# Eagle_schem_Nepixel_MIC_1_ESP8266_12.net
KiCad netlist of a schematic drawn in EAGLE
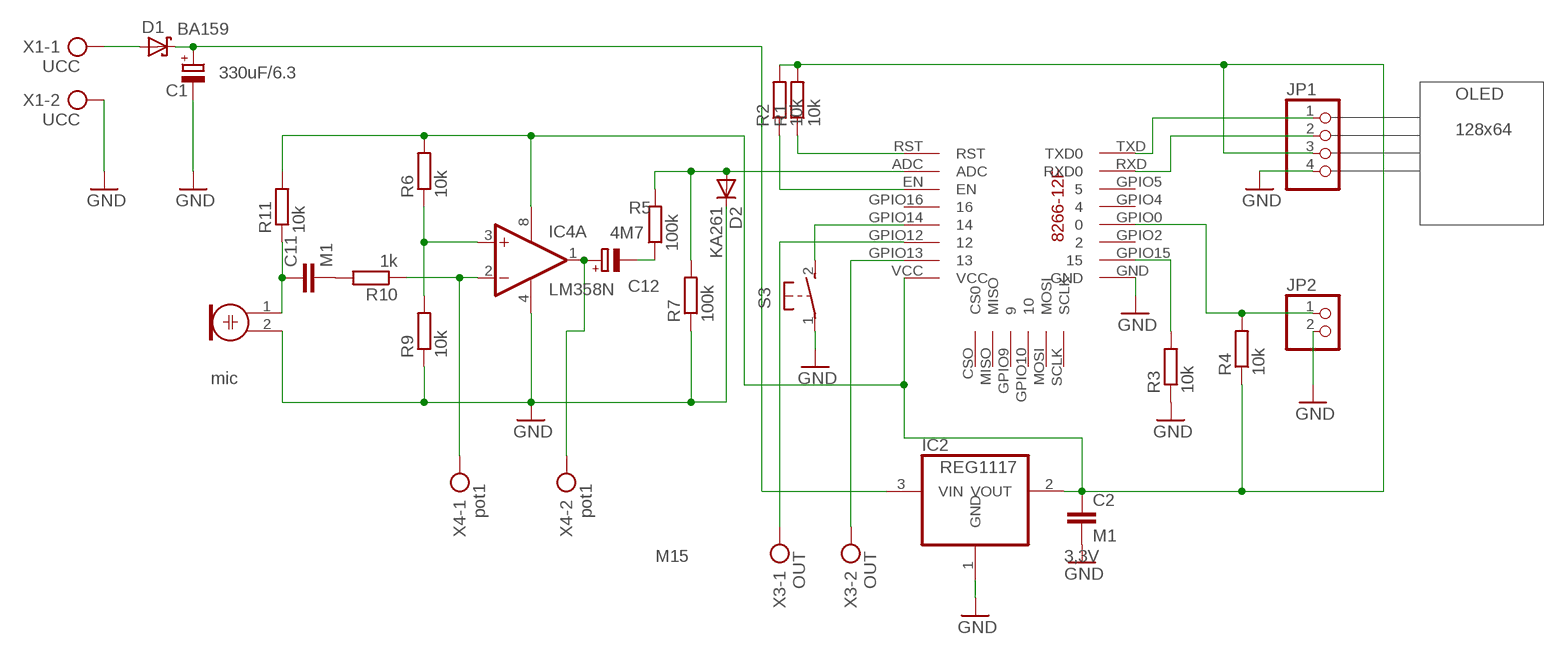
[diagram p0: schematic, sheet 1]

(export (version "E")
  (design (tool "Eeschema 10.0.6"))
  (components
    (comp (ref "C1")
      (value "330uF/6.3")
      (footprint "eagle-import:E2,5-7")
      (libsource (lib "eagle-import") (part "CPOL-EUE2.5-7"))
    )
    (comp (ref "C2")
      (value "M1")
      (footprint "eagle-import:C025-024X044")
      (libsource (lib "eagle-import") (part "C-EU025-024X044"))
    )
    (comp (ref "C11")
      (value "M1")
      (footprint "eagle-import:C025-024X044")
      (libsource (lib "eagle-import") (part "C-EU025-024X044"))
    )
    (comp (ref "C12")
      (value "4M7")
      (footprint "eagle-import:E2,5-5")
      (libsource (lib "eagle-import") (part "CPOL-EUE2.5-5"))
    )
    (comp (ref "D1")
      (value "BA159")
      (footprint "eagle-import:DO35-7")
      (libsource (lib "eagle-import") (part "SCHOTTKY-DIODEDO35-7"))
    )
    (comp (ref "D2")
      (value "KA261")
      (footprint "eagle-import:DO41-7.6")
      (libsource (lib "eagle-import") (part "DIODE-DO41-7.6"))
    )
    (comp (ref "IC2")
      (value "REG1117")
      (footprint "eagle-import:SOT223")
      (libsource (lib "eagle-import") (part "REG1117"))
    )
    (comp (ref "IC4")
      (value "LM358N")
      (footprint "eagle-import:DIL08")
      (libsource (lib "eagle-import") (part "LM358N"))
    )
    (comp (ref "JP1")
      (value "PINHD-1X4")
      (footprint "eagle-import:1X04")
      (libsource (lib "eagle-import") (part "PINHD-1X4"))
    )
    (comp (ref "JP2")
      (value "PINHD-1X2")
      (footprint "eagle-import:1X02")
      (libsource (lib "eagle-import") (part "PINHD-1X2"))
    )
    (comp (ref "M1")
      (value "mic")
      (footprint "eagle-import:WM-64PN")
      (libsource (lib "eagle-import") (part "ELECTRET_MICROPHON-WM.64PN"))
    )
    (comp (ref "R1")
      (value "10k")
      (footprint "eagle-import:0204_7")
      (libsource (lib "eagle-import") (part "R-EU_0204/7"))
    )
    (comp (ref "R2")
      (value "10k")
      (footprint "eagle-import:0204_7")
      (libsource (lib "eagle-import") (part "R-EU_0204/7"))
    )
    (comp (ref "R3")
      (value "10k")
      (footprint "eagle-import:0204_7")
      (libsource (lib "eagle-import") (part "R-EU_0204/7"))
    )
    (comp (ref "R4")
      (value "10k")
      (footprint "eagle-import:0204_7")
      (libsource (lib "eagle-import") (part "R-EU_0204/7"))
    )
    (comp (ref "R5")
      (value "100k")
      (footprint "eagle-import:0204_7")
      (libsource (lib "eagle-import") (part "R-EU_0204/7"))
    )
    (comp (ref "R6")
      (value "10k")
      (footprint "eagle-import:0204_7")
      (libsource (lib "eagle-import") (part "R-EU_0204/7"))
    )
    (comp (ref "R7")
      (value "100k")
      (footprint "eagle-import:0204_7")
      (libsource (lib "eagle-import") (part "R-EU_0204/7"))
    )
    (comp (ref "R9")
      (value "10k")
      (footprint "eagle-import:0204_7")
      (libsource (lib "eagle-import") (part "R-EU_0204/7"))
    )
    (comp (ref "R10")
      (value "1k")
      (footprint "eagle-import:0204_7")
      (libsource (lib "eagle-import") (part "R-EU_0204/7"))
    )
    (comp (ref "R11")
      (value "10k")
      (footprint "eagle-import:0204_7")
      (libsource (lib "eagle-import") (part "R-EU_0204/7"))
    )
    (comp (ref "S3")
      (value "31-XX")
      (footprint "eagle-import:B3F-31XX")
      (fields (field (name "MPN") "B3F-3100"))
      (libsource (lib "eagle-import") (part "31-XX"))
    )
    (comp (ref "U$1")
      (value "ESP826612F")
      (footprint "eagle-import:ESP826612F")
      (libsource (lib "eagle-import") (part "ESP826612F"))
    )
    (comp (ref "X1")
      (value "UCC")
      (footprint "eagle-import:AK550_2")
      (libsource (lib "eagle-import") (part "AK550/2"))
    )
    (comp (ref "X3")
      (value "OUT")
      (footprint "eagle-import:AK550_2")
      (fields (field (name "OC_FARNELL") "unknown") (field (name "OC_NEWARK") "unknown"))
      (libsource (lib "eagle-import") (part "AK550/2"))
    )
    (comp (ref "X4")
      (value "pot1")
      (footprint "eagle-import:AK550_2")
      (fields (field (name "OC_FARNELL") "unknown") (field (name "OC_NEWARK") "unknown"))
      (libsource (lib "eagle-import") (part "AK550/2"))
    )
  )
  (nets
    (net (code "1") (name "GND") (class "Default")
      (node (ref "C1") (pin "-") (pinfunction "-_-") (pintype "passive"))
      (node (ref "C2") (pin "2") (pinfunction "2_2") (pintype "passive"))
      (node (ref "D2") (pin "C") (pinfunction "C_C") (pintype "passive"))
      (node (ref "IC2") (pin "1") (pinfunction "GND_1") (pintype "power_in"))
      (node (ref "IC4") (pin "4") (pinfunction "V-_4") (pintype "power_in"))
      (node (ref "JP1") (pin "4") (pinfunction "4_4") (pintype "passive"))
      (node (ref "JP2") (pin "2") (pinfunction "2_2") (pintype "passive"))
      (node (ref "M1") (pin "2") (pinfunction "2_2") (pintype "passive"))
      (node (ref "R3") (pin "1") (pinfunction "1_1") (pintype "passive"))
      (node (ref "R7") (pin "1") (pinfunction "1_1") (pintype "passive"))
      (node (ref "R9") (pin "1") (pinfunction "1_1") (pintype "passive"))
      (node (ref "S3") (pin "1") (pinfunction "P_1") (pintype "passive"))
      (node (ref "U$1") (pin "GND") (pinfunction "GND_GND") (pintype "bidirectional"))
      (node (ref "X1") (pin "2") (pinfunction "KL_2") (pintype "passive"))
    )
    (net (code "2") (name "Net-(C11-Pad1)") (class "Default")
      (node (ref "C11") (pin "1") (pinfunction "1_1") (pintype "passive"))
      (node (ref "M1") (pin "1") (pinfunction "1_1") (pintype "passive"))
      (node (ref "R11") (pin "1") (pinfunction "1_1") (pintype "passive"))
    )
    (net (code "3") (name "Net-(C11-Pad2)") (class "Default")
      (node (ref "C11") (pin "2") (pinfunction "2_2") (pintype "passive"))
      (node (ref "R10") (pin "2") (pinfunction "2_2") (pintype "passive"))
    )
    (net (code "4") (name "Net-(C12-Pad-)") (class "Default")
      (node (ref "C12") (pin "-") (pinfunction "-_-") (pintype "passive"))
      (node (ref "R5") (pin "1") (pinfunction "1_1") (pintype "passive"))
    )
    (net (code "5") (name "Net-(D2-PadA)") (class "Default")
      (node (ref "D2") (pin "A") (pinfunction "A_A") (pintype "passive"))
      (node (ref "R5") (pin "2") (pinfunction "2_2") (pintype "passive"))
      (node (ref "R7") (pin "2") (pinfunction "2_2") (pintype "passive"))
      (node (ref "U$1") (pin "ADC") (pinfunction "ADC_ADC") (pintype "bidirectional"))
    )
    (net (code "6") (name "Net-(IC2-VIN)") (class "Default")
      (node (ref "C1") (pin "+") (pinfunction "+_+") (pintype "passive"))
      (node (ref "D1") (pin "C") (pinfunction "C_C") (pintype "passive"))
      (node (ref "IC2") (pin "3") (pinfunction "VIN_3") (pintype "input"))
    )
    (net (code "7") (name "Net-(IC2-VOUT)") (class "Default")
      (node (ref "C2") (pin "1") (pinfunction "1_1") (pintype "passive"))
      (node (ref "IC2") (pin "2") (pinfunction "VOUT_2") (pintype "output"))
      (node (ref "IC4") (pin "8") (pinfunction "V+_8") (pintype "power_in"))
      (node (ref "JP1") (pin "3") (pinfunction "3_3") (pintype "passive"))
      (node (ref "R1") (pin "2") (pinfunction "2_2") (pintype "passive"))
      (node (ref "R11") (pin "2") (pinfunction "2_2") (pintype "passive"))
      (node (ref "R2") (pin "2") (pinfunction "2_2") (pintype "passive"))
      (node (ref "R4") (pin "1") (pinfunction "1_1") (pintype "passive"))
      (node (ref "R6") (pin "2") (pinfunction "2_2") (pintype "passive"))
      (node (ref "U$1") (pin "VCC") (pinfunction "VCC_VCC") (pintype "bidirectional"))
    )
    (net (code "8") (name "Net-(IC4A-+IN)") (class "Default")
      (node (ref "IC4") (pin "3") (pinfunction "+IN_3") (pintype "input"))
      (node (ref "R6") (pin "1") (pinfunction "1_1") (pintype "passive"))
      (node (ref "R9") (pin "2") (pinfunction "2_2") (pintype "passive"))
    )
    (net (code "9") (name "Net-(IC4A--IN)") (class "Default")
      (node (ref "IC4") (pin "2") (pinfunction "-IN_2") (pintype "input"))
      (node (ref "R10") (pin "1") (pinfunction "1_1") (pintype "passive"))
      (node (ref "X4") (pin "1") (pinfunction "KL_1") (pintype "passive"))
    )
    (net (code "10") (name "Net-(IC4A-OUT)") (class "Default")
      (node (ref "C12") (pin "+") (pinfunction "+_+") (pintype "passive"))
      (node (ref "IC4") (pin "1") (pinfunction "OUT_1") (pintype "output"))
      (node (ref "X4") (pin "2") (pinfunction "KL_2") (pintype "passive"))
    )
    (net (code "11") (name "Net-(R1-Pad1)") (class "Default")
      (node (ref "R1") (pin "1") (pinfunction "1_1") (pintype "passive"))
      (node (ref "U$1") (pin "RST") (pinfunction "RST_RST") (pintype "bidirectional"))
    )
    (net (code "12") (name "Net-(R2-Pad1)") (class "Default")
      (node (ref "R2") (pin "1") (pinfunction "1_1") (pintype "passive"))
      (node (ref "U$1") (pin "EN") (pinfunction "EN_EN") (pintype "bidirectional"))
    )
    (net (code "13") (name "Net-(S3-S)") (class "Default")
      (node (ref "S3") (pin "2") (pinfunction "S_2") (pintype "passive"))
      (node (ref "U$1") (pin "GPIO14") (pinfunction "14_GPIO14") (pintype "bidirectional"))
    )
    (net (code "14") (name "Net-(U$1-0)") (class "Default")
      (node (ref "JP2") (pin "1") (pinfunction "1_1") (pintype "passive"))
      (node (ref "R4") (pin "2") (pinfunction "2_2") (pintype "passive"))
      (node (ref "U$1") (pin "GPIO0") (pinfunction "0_GPIO0") (pintype "bidirectional"))
    )
    (net (code "15") (name "Net-(U$1-12)") (class "Default")
      (node (ref "U$1") (pin "GPIO12") (pinfunction "12_GPIO12") (pintype "bidirectional"))
      (node (ref "X3") (pin "1") (pinfunction "KL_1") (pintype "passive"))
    )
    (net (code "16") (name "Net-(U$1-13)") (class "Default")
      (node (ref "U$1") (pin "GPIO13") (pinfunction "13_GPIO13") (pintype "bidirectional"))
      (node (ref "X3") (pin "2") (pinfunction "KL_2") (pintype "passive"))
    )
    (net (code "17") (name "Net-(U$1-15)") (class "Default")
      (node (ref "R3") (pin "2") (pinfunction "2_2") (pintype "passive"))
      (node (ref "U$1") (pin "GPIO15") (pinfunction "15_GPIO15") (pintype "bidirectional"))
    )
    (net (code "18") (name "Net-(U$1-RXD0)") (class "Default")
      (node (ref "JP1") (pin "2") (pinfunction "2_2") (pintype "passive"))
      (node (ref "U$1") (pin "RXD") (pinfunction "RXD0_RXD") (pintype "bidirectional"))
    )
    (net (code "19") (name "Net-(U$1-TXD0)") (class "Default")
      (node (ref "JP1") (pin "1") (pinfunction "1_1") (pintype "passive"))
      (node (ref "U$1") (pin "TXD") (pinfunction "TXD0_TXD") (pintype "bidirectional"))
    )
    (net (code "20") (name "Net-(X1A-KL)") (class "Default")
      (node (ref "D1") (pin "A") (pinfunction "A_A") (pintype "passive"))
      (node (ref "X1") (pin "1") (pinfunction "KL_1") (pintype "passive"))
    )
    (net (code "21") (name "unconnected-(U$1-2-PadGPIO2)") (class "Default")
      (node (ref "U$1") (pin "GPIO2") (pinfunction "2_GPIO2") (pintype "bidirectional"))
    )
    (net (code "22") (name "unconnected-(U$1-4-PadGPIO4)") (class "Default")
      (node (ref "U$1") (pin "GPIO4") (pinfunction "4_GPIO4") (pintype "bidirectional"))
    )
    (net (code "23") (name "unconnected-(U$1-5-PadGPIO5)") (class "Default")
      (node (ref "U$1") (pin "GPIO5") (pinfunction "5_GPIO5") (pintype "bidirectional"))
    )
    (net (code "24") (name "unconnected-(U$1-9-PadGPIO9)") (class "Default")
      (node (ref "U$1") (pin "GPIO9") (pinfunction "9_GPIO9") (pintype "bidirectional"))
    )
    (net (code "25") (name "unconnected-(U$1-10-PadGPIO10)") (class "Default")
      (node (ref "U$1") (pin "GPIO10") (pinfunction "10_GPIO10") (pintype "bidirectional"))
    )
    (net (code "26") (name "unconnected-(U$1-16-PadGPIO16)") (class "Default")
      (node (ref "U$1") (pin "GPIO16") (pinfunction "16_GPIO16") (pintype "bidirectional"))
    )
    (net (code "27") (name "unconnected-(U$1-CS0-PadCSO)") (class "Default")
      (node (ref "U$1") (pin "CSO") (pinfunction "CS0_CSO") (pintype "bidirectional"))
    )
    (net (code "28") (name "unconnected-(U$1-PadMISO)") (class "Default")
      (node (ref "U$1") (pin "MISO") (pinfunction "MISO_MISO") (pintype "bidirectional"))
    )
    (net (code "29") (name "unconnected-(U$1-PadMOSI)") (class "Default")
      (node (ref "U$1") (pin "MOSI") (pinfunction "MOSI_MOSI") (pintype "bidirectional"))
    )
    (net (code "30") (name "unconnected-(U$1-PadSCLK)") (class "Default")
      (node (ref "U$1") (pin "SCLK") (pinfunction "SCLK_SCLK") (pintype "bidirectional"))
    )
  )
)
